# EEZ_DIB_module_template_non-isolated.net
KiCad netlist of a schematic drawn in EAGLE
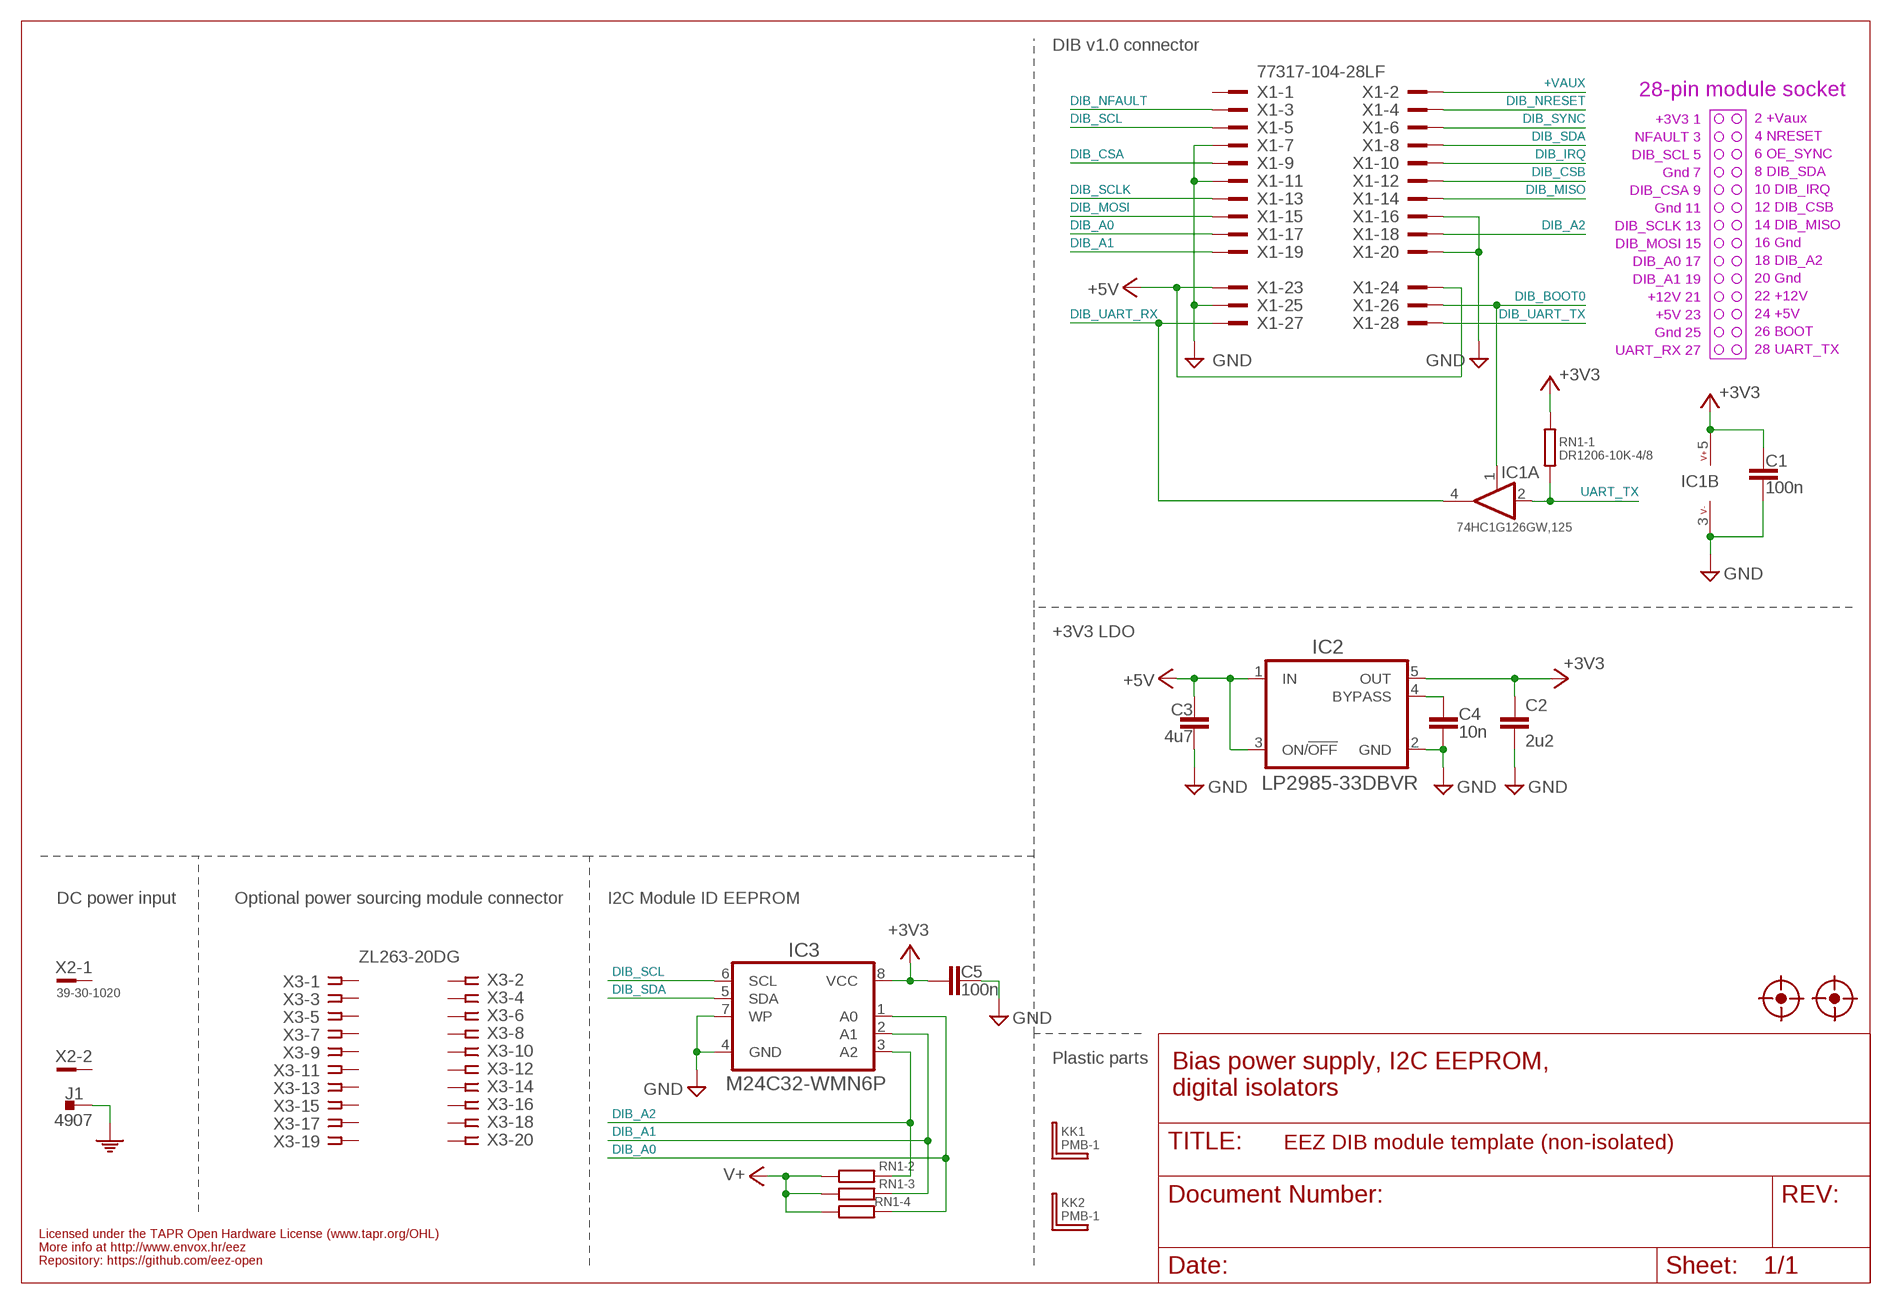
[diagram p0: schematic, sheet 1]

(export (version "E")
  (design (tool "Eeschema 10.0.6"))
  (components
    (comp (ref "C1")
      (value "100n")
      (footprint "eagle-import:C0603")
      (libsource (lib "eagle-import") (part "C-EUC0603"))
    )
    (comp (ref "C2")
      (value "2u2")
      (footprint "eagle-import:C0805")
      (libsource (lib "eagle-import") (part "C-EUC0805"))
    )
    (comp (ref "C3")
      (value "4u7")
      (footprint "eagle-import:C0805")
      (libsource (lib "eagle-import") (part "C-EUC0805"))
    )
    (comp (ref "C4")
      (value "10n")
      (footprint "eagle-import:C0805")
      (libsource (lib "eagle-import") (part "C-EUC0805"))
    )
    (comp (ref "C5")
      (value "100n")
      (footprint "eagle-import:C0603")
      (libsource (lib "eagle-import") (part "C-EUC0603"))
    )
    (comp (ref "FM1")
      (value "FIDUCIAL_2")
      (footprint "eagle-import:FIDUCIAL_DUAL")
      (libsource (lib "eagle-import") (part "FIDUCIAL_2"))
    )
    (comp (ref "FM2")
      (value "FIDUCIAL_2")
      (footprint "eagle-import:FIDUCIAL_DUAL")
      (libsource (lib "eagle-import") (part "FIDUCIAL_2"))
    )
    (comp (ref "IC1")
      (value "74HC1G126GW,125")
      (footprint "eagle-import:SOT65P210X110-5N")
      (libsource (lib "eagle-import") (part "74HC1G126GW,125"))
    )
    (comp (ref "IC2")
      (value "LP2985-33DBVR")
      (footprint "eagle-import:SOT95P270X145-5N")
      (libsource (lib "eagle-import") (part "LP2985"))
    )
    (comp (ref "IC3")
      (value "M24C32-WMN6P")
      (footprint "eagle-import:SOIC127P600X173-8N")
      (libsource (lib "eagle-import") (part "AT24CXXSOIC8"))
    )
    (comp (ref "J1")
      (value "4907")
      (footprint "eagle-import:PCB_TAB-4907")
      (libsource (lib "eagle-import") (part "PCB_TAB-4907"))
    )
    (comp (ref "KK1")
      (value "PMB-1")
      (footprint "eagle-import:PCB-MB")
      (libsource (lib "eagle-import") (part "PCB-MB"))
    )
    (comp (ref "KK2")
      (value "PMB-1")
      (footprint "eagle-import:PCB-MB")
      (libsource (lib "eagle-import") (part "PCB-MB"))
    )
    (comp (ref "RN1")
      (value "DR1206-10K-4/8")
      (footprint "eagle-import:CAY16")
      (libsource (lib "eagle-import") (part "R_ARRAY4"))
    )
    (comp (ref "X1")
      (value "77317-104-28LF")
      (footprint "eagle-import:77317-104-28LF")
      (libsource (lib "eagle-import") (part "77317-104-28LF"))
    )
    (comp (ref "X2")
      (value "39-30-1020")
      (footprint "eagle-import:MINIFIT_39301020")
      (libsource (lib "eagle-import") (part "MINIFIT_39301020"))
    )
    (comp (ref "X3")
      (value "ZL263-20DG")
      (footprint "eagle-import:SSW-110-02-T-D-RA")
      (libsource (lib "eagle-import") (part "SSW-110-02-T-D-RA"))
    )
  )
  (nets
    (net (code "1") (name "+3V3") (class "Default")
      (node (ref "C1") (pin "1") (pinfunction "1_1") (pintype "passive"))
      (node (ref "C2") (pin "1") (pinfunction "1_1") (pintype "passive"))
      (node (ref "C5") (pin "2") (pinfunction "2_2") (pintype "passive"))
      (node (ref "IC1") (pin "5") (pinfunction "V+_5") (pintype "power_in"))
      (node (ref "IC2") (pin "5") (pinfunction "OUT_5") (pintype "passive"))
      (node (ref "IC3") (pin "8") (pinfunction "VCC_8") (pintype "power_in"))
      (node (ref "RN1") (pin "8") (pinfunction "2_8") (pintype "passive"))
    )
    (net (code "2") (name "+5V") (class "Default")
      (node (ref "C3") (pin "2") (pinfunction "2_2") (pintype "passive"))
      (node (ref "IC2") (pin "1") (pinfunction "IN_1") (pintype "input"))
      (node (ref "IC2") (pin "3") (pinfunction "ON/~{OFF}_3") (pintype "input"))
      (node (ref "X1") (pin "23") (pinfunction "1_23") (pintype "passive"))
      (node (ref "X1") (pin "24") (pinfunction "1_24") (pintype "passive"))
    )
    (net (code "3") (name "/+VAUX") (class "Default")
      (node (ref "X1") (pin "2") (pinfunction "1_2") (pintype "passive"))
    )
    (net (code "4") (name "/DIB_A0") (class "Default")
      (node (ref "IC3") (pin "1") (pinfunction "A0_1") (pintype "input"))
      (node (ref "RN1") (pin "4") (pinfunction "1_4") (pintype "passive"))
      (node (ref "X1") (pin "17") (pinfunction "1_17") (pintype "passive"))
    )
    (net (code "5") (name "/DIB_A1") (class "Default")
      (node (ref "IC3") (pin "2") (pinfunction "A1_2") (pintype "input"))
      (node (ref "RN1") (pin "3") (pinfunction "1_3") (pintype "passive"))
      (node (ref "X1") (pin "19") (pinfunction "1_19") (pintype "passive"))
    )
    (net (code "6") (name "/DIB_A2") (class "Default")
      (node (ref "IC3") (pin "3") (pinfunction "A2_3") (pintype "input"))
      (node (ref "RN1") (pin "2") (pinfunction "1_2") (pintype "passive"))
      (node (ref "X1") (pin "18") (pinfunction "1_18") (pintype "passive"))
    )
    (net (code "7") (name "/DIB_BOOT0") (class "Default")
      (node (ref "IC1") (pin "1") (pinfunction "EN_1") (pintype "input"))
      (node (ref "X1") (pin "26") (pinfunction "1_26") (pintype "passive"))
    )
    (net (code "8") (name "/DIB_CSA") (class "Default")
      (node (ref "X1") (pin "9") (pinfunction "1_9") (pintype "passive"))
    )
    (net (code "9") (name "/DIB_CSB") (class "Default")
      (node (ref "X1") (pin "12") (pinfunction "1_12") (pintype "passive"))
    )
    (net (code "10") (name "/DIB_IRQ") (class "Default")
      (node (ref "X1") (pin "10") (pinfunction "1_10") (pintype "passive"))
    )
    (net (code "11") (name "/DIB_MISO") (class "Default")
      (node (ref "X1") (pin "14") (pinfunction "1_14") (pintype "passive"))
    )
    (net (code "12") (name "/DIB_MOSI") (class "Default")
      (node (ref "X1") (pin "15") (pinfunction "1_15") (pintype "passive"))
    )
    (net (code "13") (name "/DIB_NFAULT") (class "Default")
      (node (ref "X1") (pin "3") (pinfunction "1_3") (pintype "passive"))
    )
    (net (code "14") (name "/DIB_NRESET") (class "Default")
      (node (ref "X1") (pin "4") (pinfunction "1_4") (pintype "passive"))
    )
    (net (code "15") (name "/DIB_SCL") (class "Default")
      (node (ref "IC3") (pin "6") (pinfunction "SCL_6") (pintype "bidirectional"))
      (node (ref "X1") (pin "5") (pinfunction "1_5") (pintype "passive"))
    )
    (net (code "16") (name "/DIB_SCLK") (class "Default")
      (node (ref "X1") (pin "13") (pinfunction "1_13") (pintype "passive"))
    )
    (net (code "17") (name "/DIB_SDA") (class "Default")
      (node (ref "IC3") (pin "5") (pinfunction "SDA_5") (pintype "bidirectional"))
      (node (ref "X1") (pin "8") (pinfunction "1_8") (pintype "passive"))
    )
    (net (code "18") (name "/DIB_SYNC") (class "Default")
      (node (ref "X1") (pin "6") (pinfunction "1_6") (pintype "passive"))
    )
    (net (code "19") (name "/DIB_UART_RX") (class "Default")
      (node (ref "IC1") (pin "4") (pinfunction "O_4") (pintype "output"))
      (node (ref "X1") (pin "27") (pinfunction "1_27") (pintype "passive"))
    )
    (net (code "20") (name "/DIB_UART_TX") (class "Default")
      (node (ref "X1") (pin "28") (pinfunction "1_28") (pintype "passive"))
    )
    (net (code "21") (name "/UART_TX") (class "Default")
      (node (ref "IC1") (pin "2") (pinfunction "I_2") (pintype "input"))
      (node (ref "RN1") (pin "1") (pinfunction "1_1") (pintype "passive"))
    )
    (net (code "22") (name "GND") (class "Default")
      (node (ref "C1") (pin "2") (pinfunction "2_2") (pintype "passive"))
      (node (ref "C2") (pin "2") (pinfunction "2_2") (pintype "passive"))
      (node (ref "C3") (pin "1") (pinfunction "1_1") (pintype "passive"))
      (node (ref "C4") (pin "1") (pinfunction "1_1") (pintype "passive"))
      (node (ref "C5") (pin "1") (pinfunction "1_1") (pintype "passive"))
      (node (ref "IC1") (pin "3") (pinfunction "V-_3") (pintype "power_in"))
      (node (ref "IC2") (pin "2") (pinfunction "GND_2") (pintype "passive"))
      (node (ref "IC3") (pin "4") (pinfunction "GND_4") (pintype "passive"))
      (node (ref "IC3") (pin "7") (pinfunction "WP_7") (pintype "input"))
      (node (ref "X1") (pin "11") (pinfunction "1_11") (pintype "passive"))
      (node (ref "X1") (pin "16") (pinfunction "1_16") (pintype "passive"))
      (node (ref "X1") (pin "20") (pinfunction "1_20") (pintype "passive"))
      (node (ref "X1") (pin "25") (pinfunction "1_25") (pintype "passive"))
      (node (ref "X1") (pin "7") (pinfunction "1_7") (pintype "passive"))
    )
    (net (code "23") (name "Net-(IC2-BYPASS)") (class "Default")
      (node (ref "C4") (pin "2") (pinfunction "2_2") (pintype "passive"))
      (node (ref "IC2") (pin "4") (pinfunction "BYPASS_4") (pintype "passive"))
    )
    (net (code "24") (name "PE") (class "Default")
      (node (ref "J1") (pin "1") (pinfunction "P$1_1") (pintype "bidirectional"))
      (node (ref "J1") (pin "2") (pinfunction "P$1_2") (pintype "bidirectional"))
    )
    (net (code "25") (name "V+") (class "Default")
      (node (ref "RN1") (pin "5") (pinfunction "2_5") (pintype "passive"))
      (node (ref "RN1") (pin "6") (pinfunction "2_6") (pintype "passive"))
      (node (ref "RN1") (pin "7") (pinfunction "2_7") (pintype "passive"))
    )
    (net (code "26") (name "unconnected-(X1-Pad1)") (class "Default")
      (node (ref "X1") (pin "1") (pinfunction "1_1") (pintype "passive"))
    )
    (net (code "27") (name "unconnected-(X2-Pad1)") (class "Default")
      (node (ref "X2") (pin "1") (pinfunction "1_1") (pintype "passive"))
    )
    (net (code "28") (name "unconnected-(X2B-1-Pad2)") (class "Default")
      (node (ref "X2") (pin "2") (pinfunction "1_2") (pintype "passive"))
    )
    (net (code "29") (name "unconnected-(X3-Pad1)") (class "Default")
      (node (ref "X3") (pin "1") (pinfunction "1_1") (pintype "passive"))
    )
    (net (code "30") (name "unconnected-(X3B-1-Pad10)") (class "Default")
      (node (ref "X3") (pin "10") (pinfunction "1_10") (pintype "passive"))
    )
    (net (code "31") (name "unconnected-(X3C-1-Pad11)") (class "Default")
      (node (ref "X3") (pin "11") (pinfunction "1_11") (pintype "passive"))
    )
    (net (code "32") (name "unconnected-(X3D-1-Pad12)") (class "Default")
      (node (ref "X3") (pin "12") (pinfunction "1_12") (pintype "passive"))
    )
    (net (code "33") (name "unconnected-(X3E-1-Pad13)") (class "Default")
      (node (ref "X3") (pin "13") (pinfunction "1_13") (pintype "passive"))
    )
    (net (code "34") (name "unconnected-(X3F-1-Pad14)") (class "Default")
      (node (ref "X3") (pin "14") (pinfunction "1_14") (pintype "passive"))
    )
    (net (code "35") (name "unconnected-(X3G-1-Pad15)") (class "Default")
      (node (ref "X3") (pin "15") (pinfunction "1_15") (pintype "passive"))
    )
    (net (code "36") (name "unconnected-(X3H-1-Pad16)") (class "Default")
      (node (ref "X3") (pin "16") (pinfunction "1_16") (pintype "passive"))
    )
    (net (code "37") (name "unconnected-(X3I-1-Pad17)") (class "Default")
      (node (ref "X3") (pin "17") (pinfunction "1_17") (pintype "passive"))
    )
    (net (code "38") (name "unconnected-(X3J-1-Pad18)") (class "Default")
      (node (ref "X3") (pin "18") (pinfunction "1_18") (pintype "passive"))
    )
    (net (code "39") (name "unconnected-(X3K-1-Pad19)") (class "Default")
      (node (ref "X3") (pin "19") (pinfunction "1_19") (pintype "passive"))
    )
    (net (code "40") (name "unconnected-(X3L-1-Pad2)") (class "Default")
      (node (ref "X3") (pin "2") (pinfunction "1_2") (pintype "passive"))
    )
    (net (code "41") (name "unconnected-(X3M-1-Pad20)") (class "Default")
      (node (ref "X3") (pin "20") (pinfunction "1_20") (pintype "passive"))
    )
    (net (code "42") (name "unconnected-(X3N-1-Pad3)") (class "Default")
      (node (ref "X3") (pin "3") (pinfunction "1_3") (pintype "passive"))
    )
    (net (code "43") (name "unconnected-(X3O-1-Pad4)") (class "Default")
      (node (ref "X3") (pin "4") (pinfunction "1_4") (pintype "passive"))
    )
    (net (code "44") (name "unconnected-(X3P-1-Pad5)") (class "Default")
      (node (ref "X3") (pin "5") (pinfunction "1_5") (pintype "passive"))
    )
    (net (code "45") (name "unconnected-(X3Q-1-Pad6)") (class "Default")
      (node (ref "X3") (pin "6") (pinfunction "1_6") (pintype "passive"))
    )
    (net (code "46") (name "unconnected-(X3R-1-Pad7)") (class "Default")
      (node (ref "X3") (pin "7") (pinfunction "1_7") (pintype "passive"))
    )
    (net (code "47") (name "unconnected-(X3S-1-Pad8)") (class "Default")
      (node (ref "X3") (pin "8") (pinfunction "1_8") (pintype "passive"))
    )
    (net (code "48") (name "unconnected-(X3T-1-Pad9)") (class "Default")
      (node (ref "X3") (pin "9") (pinfunction "1_9") (pintype "passive"))
    )
  )
)
